# Window.net
KiCad netlist of a schematic drawn in EAGLE
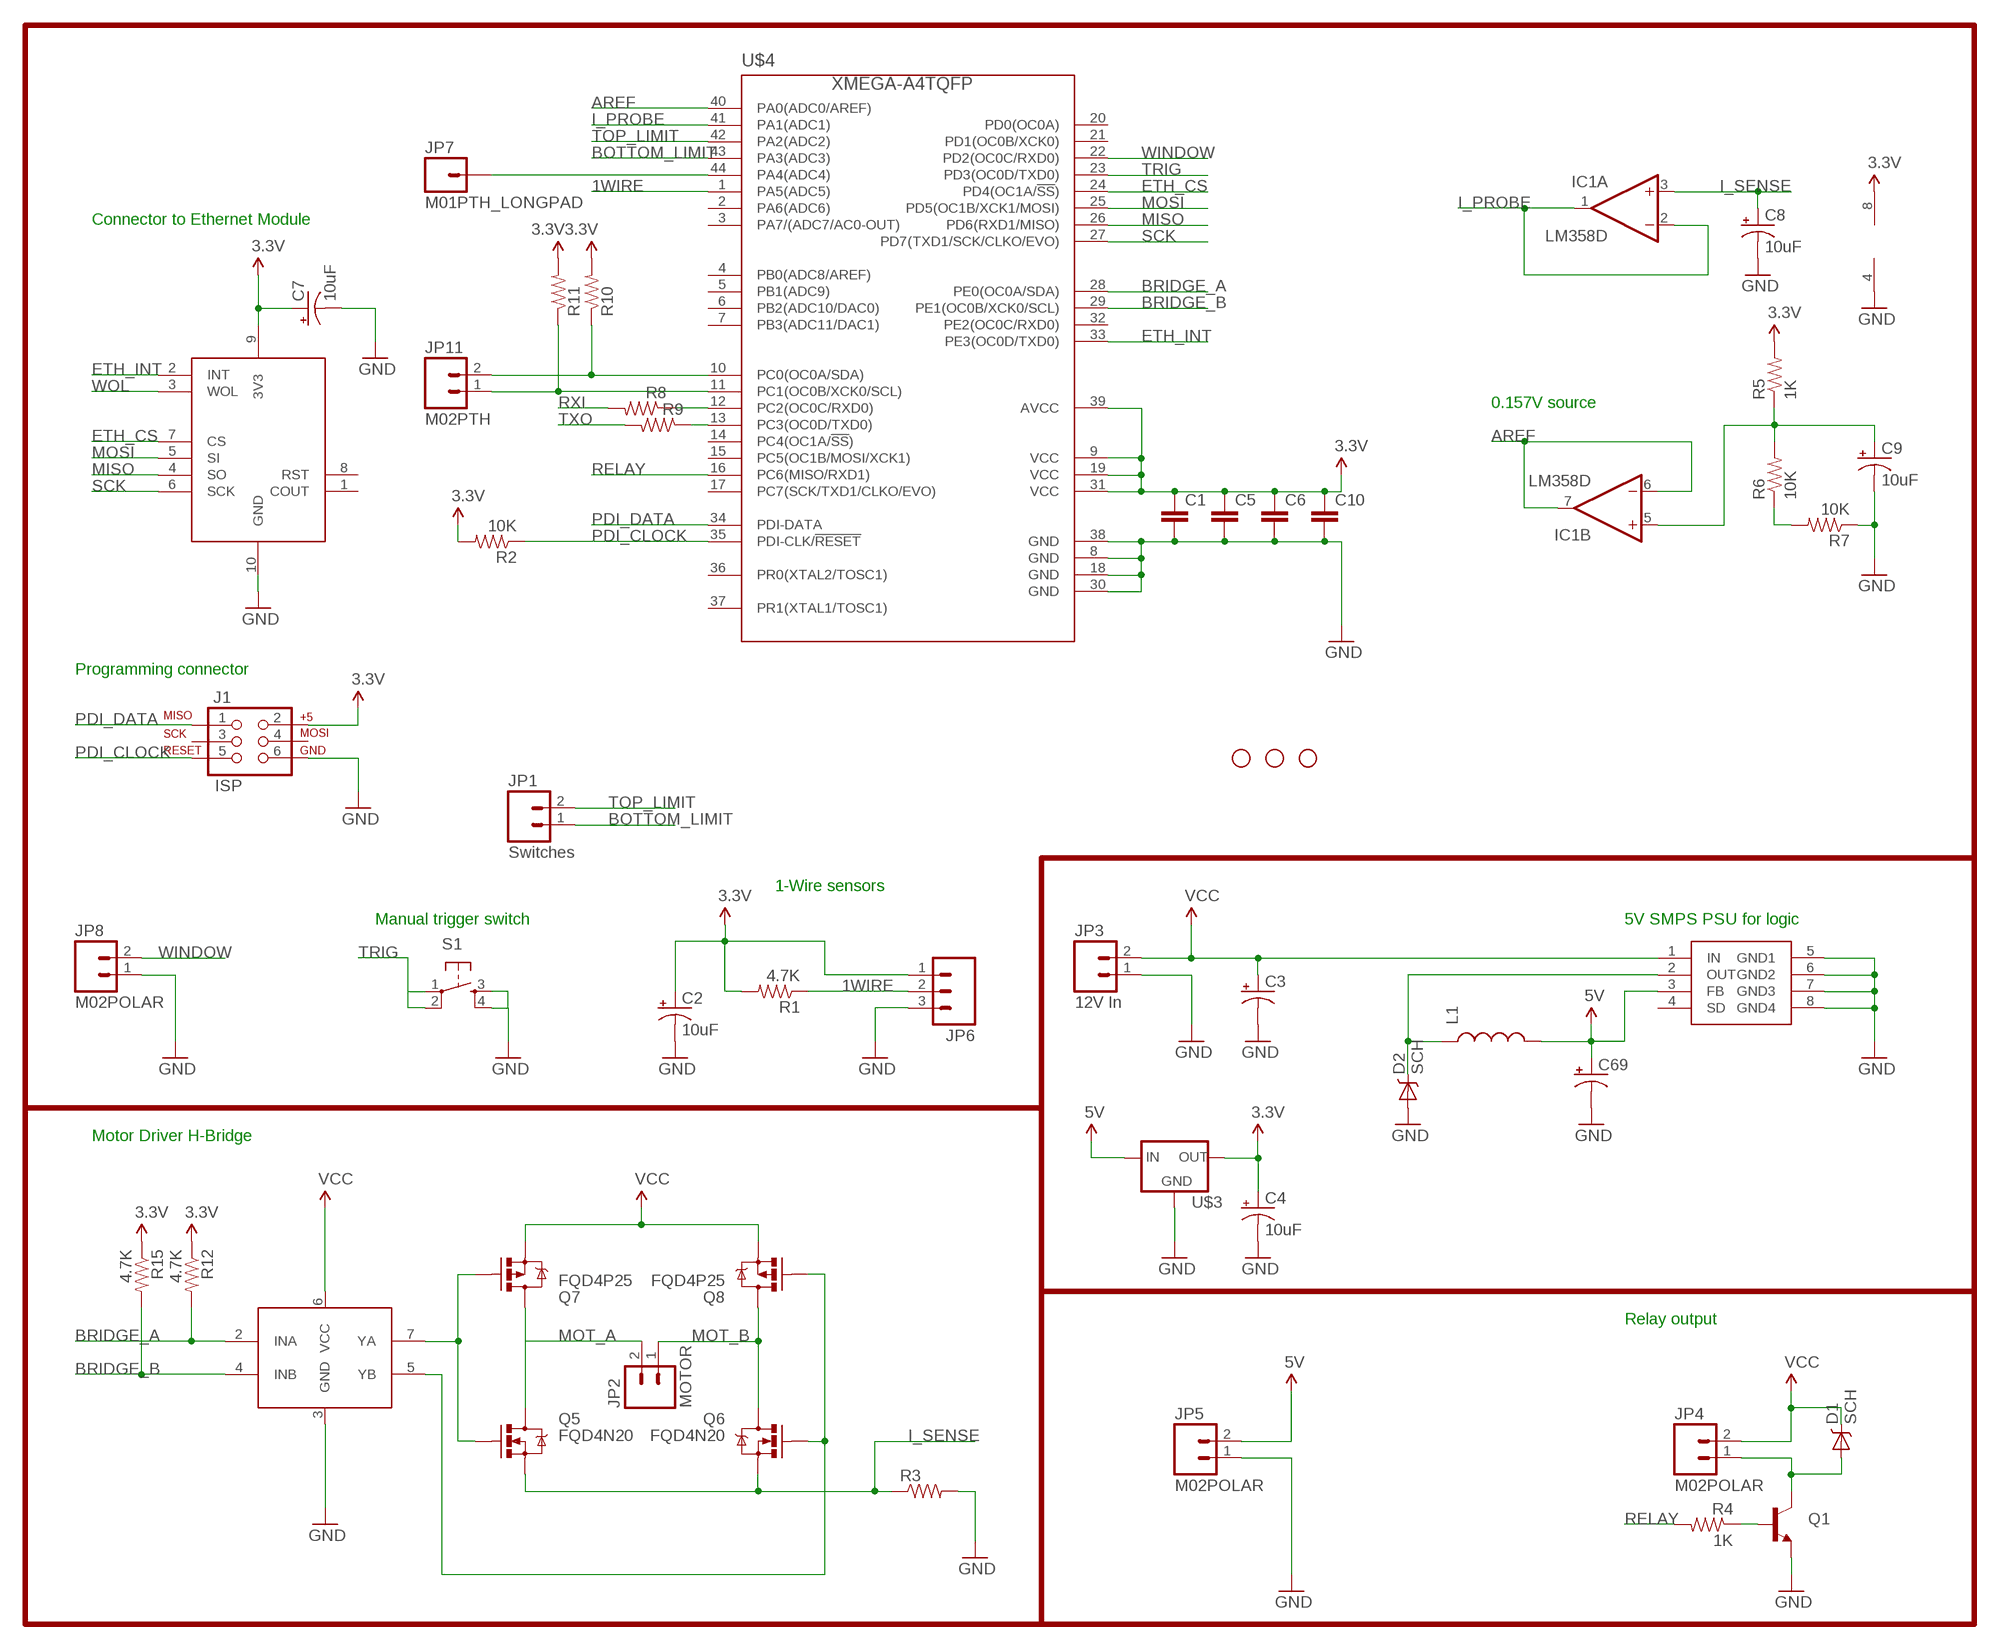
[diagram p0: schematic, sheet 1, part 1 of 2]
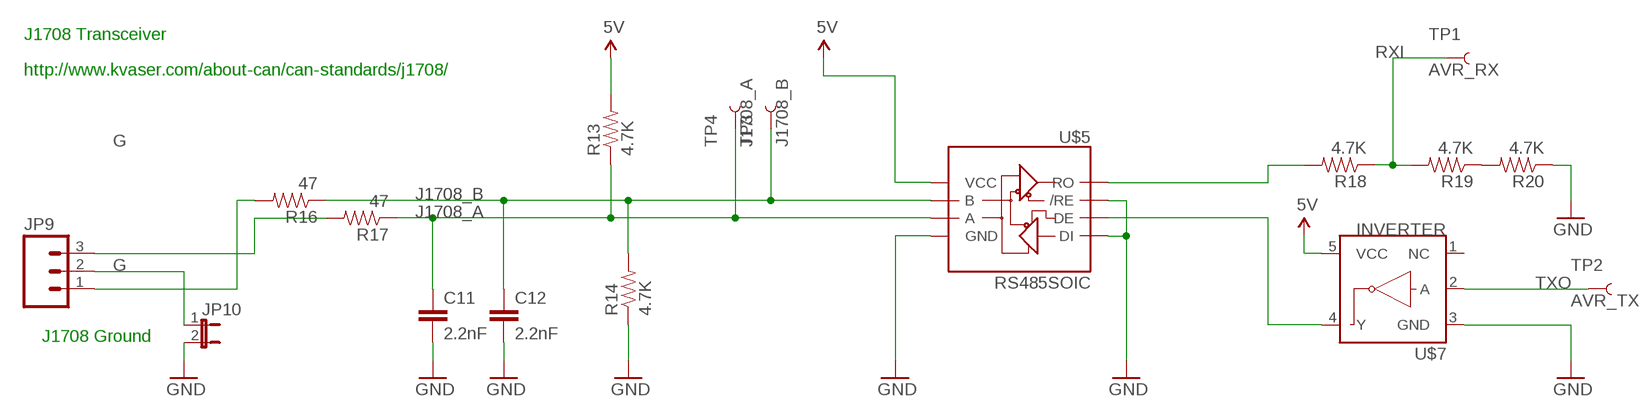
[diagram p1: schematic, sheet 1, part 2 of 2]

(export (version "E")
  (design (tool "Eeschema 10.0.6"))
  (components
    (comp (ref "C1")
      (value "CAP0603-CAP")
      (footprint "eagle-import:0603-CAP")
      (libsource (lib "eagle-import") (part "CAP0603-CAP"))
    )
    (comp (ref "C2")
      (value "10uF")
      (footprint "eagle-import:EIA3216")
      (libsource (lib "eagle-import") (part "CAP_POL1206"))
    )
    (comp (ref "C3")
      (value "CAP_POLPTH1")
      (footprint "eagle-import:CPOL-RADIAL-100UF-25V")
      (libsource (lib "eagle-import") (part "CAP_POLPTH1"))
    )
    (comp (ref "C4")
      (value "10uF")
      (footprint "eagle-import:EIA3216")
      (libsource (lib "eagle-import") (part "CAP_POL1206"))
    )
    (comp (ref "C5")
      (value "CAP0603-CAP")
      (footprint "eagle-import:0603-CAP")
      (libsource (lib "eagle-import") (part "CAP0603-CAP"))
    )
    (comp (ref "C6")
      (value "CAP0603-CAP")
      (footprint "eagle-import:0603-CAP")
      (libsource (lib "eagle-import") (part "CAP0603-CAP"))
    )
    (comp (ref "C7")
      (value "10uF")
      (footprint "eagle-import:EIA3216")
      (libsource (lib "eagle-import") (part "CAP_POL1206"))
    )
    (comp (ref "C8")
      (value "10uF")
      (footprint "eagle-import:EIA3216")
      (libsource (lib "eagle-import") (part "CAP_POL1206"))
    )
    (comp (ref "C9")
      (value "10uF")
      (footprint "eagle-import:EIA3216")
      (libsource (lib "eagle-import") (part "CAP_POL1206"))
    )
    (comp (ref "C10")
      (value "CAP0603-CAP")
      (footprint "eagle-import:0603-CAP")
      (libsource (lib "eagle-import") (part "CAP0603-CAP"))
    )
    (comp (ref "C11")
      (value "2.2nF")
      (footprint "eagle-import:0603-CAP")
      (libsource (lib "eagle-import") (part "CAP0603-CAP"))
    )
    (comp (ref "C12")
      (value "2.2nF")
      (footprint "eagle-import:0603-CAP")
      (libsource (lib "eagle-import") (part "CAP0603-CAP"))
    )
    (comp (ref "C69")
      (value "CAP_POLPTH1")
      (footprint "eagle-import:CPOL-RADIAL-100UF-25V")
      (libsource (lib "eagle-import") (part "CAP_POLPTH1"))
    )
    (comp (ref "D1")
      (value "SCH")
      (footprint "eagle-import:SMA-DIODE")
      (libsource (lib "eagle-import") (part "DIODE-SCHOTTKY_"))
    )
    (comp (ref "D2")
      (value "SCH")
      (footprint "eagle-import:SMA-DIODE")
      (libsource (lib "eagle-import") (part "DIODE-SCHOTTKY_"))
    )
    (comp (ref "IC1")
      (value "LM358D")
      (footprint "eagle-import:SO08")
      (libsource (lib "eagle-import") (part "LM358D"))
    )
    (comp (ref "J1")
      (value "ISP")
      (footprint "eagle-import:2X3")
      (libsource (lib "eagle-import") (part "AVR_SPI_PRG_6PTH"))
    )
    (comp (ref "JP1")
      (value "Switches")
      (footprint "eagle-import:SCREWTERMINAL-3.5MM-2")
      (libsource (lib "eagle-import") (part "M023.5MM"))
    )
    (comp (ref "JP2")
      (value "MOTOR")
      (footprint "eagle-import:SCREWTERMINAL-3.5MM-2")
      (libsource (lib "eagle-import") (part "M023.5MM"))
    )
    (comp (ref "JP3")
      (value "12V In")
      (footprint "eagle-import:SCREWTERMINAL-3.5MM-2")
      (libsource (lib "eagle-import") (part "M023.5MM"))
    )
    (comp (ref "JP4")
      (value "M02POLAR")
      (footprint "eagle-import:MOLEX-1X2")
      (libsource (lib "eagle-import") (part "M02POLAR"))
    )
    (comp (ref "JP5")
      (value "M02POLAR")
      (footprint "eagle-import:MOLEX-1X2")
      (libsource (lib "eagle-import") (part "M02POLAR"))
    )
    (comp (ref "JP6")
      (value "M03POLAR")
      (footprint "eagle-import:MOLEX-1X3")
      (libsource (lib "eagle-import") (part "M03POLAR"))
    )
    (comp (ref "JP7")
      (value "M01PTH_LONGPAD")
      (footprint "eagle-import:1X01_LONGPAD")
      (libsource (lib "eagle-import") (part "M01PTH_LONGPAD"))
    )
    (comp (ref "JP8")
      (value "M02POLAR")
      (footprint "eagle-import:MOLEX-1X2")
      (libsource (lib "eagle-import") (part "M02POLAR"))
    )
    (comp (ref "JP9")
      (value "M03POLAR")
      (footprint "eagle-import:MOLEX-1X3")
      (libsource (lib "eagle-import") (part "M03POLAR"))
    )
    (comp (ref "JP10")
      (value "JUMPER-2PTH")
      (footprint "eagle-import:1X02")
      (libsource (lib "eagle-import") (part "JUMPER-2PTH"))
    )
    (comp (ref "JP11")
      (value "M02PTH")
      (footprint "eagle-import:1X02")
      (libsource (lib "eagle-import") (part "M02PTH"))
    )
    (comp (ref "L1")
      (value "INDUCTOR1206H*")
      (footprint "eagle-import:INDUCTOR-1206")
      (libsource (lib "eagle-import") (part "INDUCTORH1206"))
    )
    (comp (ref "Q1")
      (value "TRANSISTOR_NPNSOT23")
      (footprint "eagle-import:SOT23")
      (libsource (lib "eagle-import") (part "TRANSISTOR_NPNSOT23"))
    )
    (comp (ref "Q5")
      (value "FQD4N20")
      (footprint "eagle-import:DPAK")
      (libsource (lib "eagle-import") (part "MOSFET-NCHANNELFDD8780"))
    )
    (comp (ref "Q6")
      (value "FQD4N20")
      (footprint "eagle-import:DPAK")
      (libsource (lib "eagle-import") (part "MOSFET-NCHANNELFDD8780"))
    )
    (comp (ref "Q7")
      (value "FQD4P25")
      (footprint "eagle-import:DPAK")
      (libsource (lib "eagle-import") (part "MOSFET-PCHANNEL"))
    )
    (comp (ref "Q8")
      (value "FQD4P25")
      (footprint "eagle-import:DPAK")
      (libsource (lib "eagle-import") (part "MOSFET-PCHANNEL"))
    )
    (comp (ref "R1")
      (value "4.7K")
      (footprint "eagle-import:1206")
      (libsource (lib "eagle-import") (part "RESISTOR1206"))
    )
    (comp (ref "R2")
      (value "10K")
      (footprint "eagle-import:1206")
      (libsource (lib "eagle-import") (part "RESISTOR1206"))
    )
    (comp (ref "R3")
      (value "RESISTORPTH-1W")
      (footprint "eagle-import:AXIAL-0.6")
      (libsource (lib "eagle-import") (part "RESISTORPTH-1W"))
    )
    (comp (ref "R4")
      (value "1K")
      (footprint "eagle-import:1206")
      (libsource (lib "eagle-import") (part "RESISTOR1206"))
    )
    (comp (ref "R5")
      (value "1K")
      (footprint "eagle-import:1206")
      (libsource (lib "eagle-import") (part "RESISTOR1206"))
    )
    (comp (ref "R6")
      (value "10K")
      (footprint "eagle-import:1206")
      (libsource (lib "eagle-import") (part "RESISTOR1206"))
    )
    (comp (ref "R7")
      (value "10K")
      (footprint "eagle-import:1206")
      (libsource (lib "eagle-import") (part "RESISTOR1206"))
    )
    (comp (ref "R8")
      (value "RESISTOR0603-RES")
      (footprint "eagle-import:0603-RES")
      (libsource (lib "eagle-import") (part "RESISTOR0603-RES"))
    )
    (comp (ref "R9")
      (value "RESISTOR0603-RES")
      (footprint "eagle-import:0603-RES")
      (libsource (lib "eagle-import") (part "RESISTOR0603-RES"))
    )
    (comp (ref "R10")
      (value "RESISTOR0603-RES")
      (footprint "eagle-import:0603-RES")
      (libsource (lib "eagle-import") (part "RESISTOR0603-RES"))
    )
    (comp (ref "R11")
      (value "RESISTOR0603-RES")
      (footprint "eagle-import:0603-RES")
      (libsource (lib "eagle-import") (part "RESISTOR0603-RES"))
    )
    (comp (ref "R12")
      (value "4.7K")
      (footprint "eagle-import:1206")
      (libsource (lib "eagle-import") (part "RESISTOR1206"))
    )
    (comp (ref "R13")
      (value "4.7K")
      (footprint "eagle-import:1206")
      (libsource (lib "eagle-import") (part "RESISTOR1206"))
    )
    (comp (ref "R14")
      (value "4.7K")
      (footprint "eagle-import:1206")
      (libsource (lib "eagle-import") (part "RESISTOR1206"))
    )
    (comp (ref "R15")
      (value "4.7K")
      (footprint "eagle-import:1206")
      (libsource (lib "eagle-import") (part "RESISTOR1206"))
    )
    (comp (ref "R16")
      (value "47")
      (footprint "eagle-import:1206")
      (libsource (lib "eagle-import") (part "RESISTOR1206"))
    )
    (comp (ref "R17")
      (value "47")
      (footprint "eagle-import:1206")
      (libsource (lib "eagle-import") (part "RESISTOR1206"))
    )
    (comp (ref "R18")
      (value "4.7K")
      (footprint "eagle-import:1206")
      (libsource (lib "eagle-import") (part "RESISTOR1206"))
    )
    (comp (ref "R19")
      (value "4.7K")
      (footprint "eagle-import:1206")
      (libsource (lib "eagle-import") (part "RESISTOR1206"))
    )
    (comp (ref "R20")
      (value "4.7K")
      (footprint "eagle-import:1206")
      (libsource (lib "eagle-import") (part "RESISTOR1206"))
    )
    (comp (ref "S1")
      (value "TAC_SWITCHPTH")
      (footprint "eagle-import:TACTILE-PTH")
      (libsource (lib "eagle-import") (part "TAC_SWITCHPTH"))
    )
    (comp (ref "STANDOFF2")
      (value "STAND-OFF")
      (footprint "eagle-import:STAND-OFF")
      (libsource (lib "eagle-import") (part "STAND-OFF"))
    )
    (comp (ref "STANDOFF3")
      (value "STAND-OFF")
      (footprint "eagle-import:STAND-OFF")
      (libsource (lib "eagle-import") (part "STAND-OFF"))
    )
    (comp (ref "STANDOFF4")
      (value "STAND-OFF")
      (footprint "eagle-import:STAND-OFF")
      (libsource (lib "eagle-import") (part "STAND-OFF"))
    )
    (comp (ref "TP1")
      (value "AVR_RX")
      (footprint "eagle-import:PAD.03X.05")
      (libsource (lib "eagle-import") (part "TEST-POINT3X5"))
    )
    (comp (ref "TP2")
      (value "AVR_TX")
      (footprint "eagle-import:PAD.03X.05")
      (libsource (lib "eagle-import") (part "TEST-POINT3X5"))
    )
    (comp (ref "TP3")
      (value "J1708_B")
      (footprint "eagle-import:PAD.03X.05")
      (libsource (lib "eagle-import") (part "TEST-POINT3X5"))
    )
    (comp (ref "TP4")
      (value "J1708_A")
      (footprint "eagle-import:PAD.03X.05")
      (libsource (lib "eagle-import") (part "TEST-POINT3X5"))
    )
    (comp (ref "U$1")
      (value "ETHMODULE")
      (footprint "eagle-import:2X5")
      (libsource (lib "eagle-import") (part "ETHMODULE"))
    )
    (comp (ref "U$2")
      (value "AP1509-33")
      (footprint "eagle-import:SOIC-8")
      (libsource (lib "eagle-import") (part "AP1509-33"))
    )
    (comp (ref "U$3")
      (value "V_REG_MIC2920")
      (footprint "eagle-import:SOT223")
      (libsource (lib "eagle-import") (part "V_REG_MIC2920"))
    )
    (comp (ref "U$4")
      (value "XMEGA-A4TQFP")
      (footprint "eagle-import:TQFP44")
      (libsource (lib "eagle-import") (part "XMEGA-A4TQFP"))
    )
    (comp (ref "U$5")
      (value "RS485SOIC")
      (footprint "eagle-import:SO08")
      (libsource (lib "eagle-import") (part "RS485SOIC"))
    )
    (comp (ref "U$6")
      (value "4427")
      (footprint "eagle-import:SOIC-8")
      (libsource (lib "eagle-import") (part "4427"))
    )
    (comp (ref "U$7")
      (value "INVERTER")
      (footprint "eagle-import:SOT23-5")
      (libsource (lib "eagle-import") (part "INVERTER"))
    )
  )
  (nets
    (net (code "1") (name "/1WIRE") (class "Default")
      (node (ref "JP6") (pin "2") (pinfunction "2_2") (pintype "passive"))
      (node (ref "R1") (pin "1") (pinfunction "1_1") (pintype "passive"))
      (node (ref "U$4") (pin "1") (pinfunction "PA5(ADC5)_1") (pintype "bidirectional"))
    )
    (net (code "2") (name "/AREF") (class "Default")
      (node (ref "IC1") (pin "6") (pinfunction "-IN_6") (pintype "input"))
      (node (ref "IC1") (pin "7") (pinfunction "OUT_7") (pintype "output"))
      (node (ref "U$4") (pin "40") (pinfunction "PA0(ADC0/AREF)_40") (pintype "bidirectional"))
    )
    (net (code "3") (name "/BOTTOM_LIMIT") (class "Default")
      (node (ref "JP1") (pin "1") (pinfunction "1_1") (pintype "passive"))
      (node (ref "U$4") (pin "43") (pinfunction "PA3(ADC3)_43") (pintype "bidirectional"))
    )
    (net (code "4") (name "/BRIDGE_A") (class "Default")
      (node (ref "R12") (pin "2") (pinfunction "2_2") (pintype "passive"))
      (node (ref "U$4") (pin "28") (pinfunction "PE0(OC0A/SDA)_28") (pintype "bidirectional"))
      (node (ref "U$6") (pin "2") (pinfunction "INA_2") (pintype "bidirectional"))
    )
    (net (code "5") (name "/BRIDGE_B") (class "Default")
      (node (ref "R15") (pin "2") (pinfunction "2_2") (pintype "passive"))
      (node (ref "U$4") (pin "29") (pinfunction "PE1(OC0B/XCK0/SCL)_29") (pintype "bidirectional"))
      (node (ref "U$6") (pin "4") (pinfunction "INB_4") (pintype "bidirectional"))
    )
    (net (code "6") (name "/COUT") (class "Default")
      (node (ref "U$1") (pin "1") (pinfunction "COUT_1") (pintype "power_in"))
    )
    (net (code "7") (name "/ETH_CS") (class "Default")
      (node (ref "U$1") (pin "7") (pinfunction "CS_7") (pintype "power_in"))
      (node (ref "U$4") (pin "24") (pinfunction "PD4(OC1A/~{SS})_24") (pintype "bidirectional"))
    )
    (net (code "8") (name "/ETH_INT") (class "Default")
      (node (ref "U$1") (pin "2") (pinfunction "INT_2") (pintype "power_in"))
      (node (ref "U$4") (pin "33") (pinfunction "PE3(OC0D/TXD0)_33") (pintype "bidirectional"))
    )
    (net (code "9") (name "/G") (class "Default")
      (node (ref "JP10") (pin "1") (pinfunction "1_1") (pintype "passive"))
      (node (ref "JP9") (pin "2") (pinfunction "2_2") (pintype "passive"))
    )
    (net (code "10") (name "/I_PROBE") (class "Default")
      (node (ref "IC1") (pin "1") (pinfunction "OUT_1") (pintype "output"))
      (node (ref "IC1") (pin "2") (pinfunction "-IN_2") (pintype "input"))
      (node (ref "U$4") (pin "41") (pinfunction "PA1(ADC1)_41") (pintype "bidirectional"))
    )
    (net (code "11") (name "/I_SENSE") (class "Default")
      (node (ref "C8") (pin "A") (pinfunction "+_A") (pintype "passive"))
      (node (ref "IC1") (pin "3") (pinfunction "+IN_3") (pintype "input"))
      (node (ref "Q5") (pin "3") (pinfunction "S_3") (pintype "passive"))
      (node (ref "Q6") (pin "3") (pinfunction "S_3") (pintype "passive"))
      (node (ref "R3") (pin "P$1") (pinfunction "1_P$1") (pintype "passive"))
    )
    (net (code "12") (name "/J1708_A") (class "Default")
      (node (ref "C11") (pin "1") (pinfunction "1_1") (pintype "passive"))
      (node (ref "R13") (pin "1") (pinfunction "1_1") (pintype "passive"))
      (node (ref "R17") (pin "1") (pinfunction "1_1") (pintype "passive"))
      (node (ref "TP4") (pin "P$1") (pinfunction "1_P$1") (pintype "bidirectional"))
      (node (ref "U$5") (pin "6") (pinfunction "A_6") (pintype "bidirectional"))
    )
    (net (code "13") (name "/J1708_B") (class "Default")
      (node (ref "C12") (pin "1") (pinfunction "1_1") (pintype "passive"))
      (node (ref "R14") (pin "2") (pinfunction "2_2") (pintype "passive"))
      (node (ref "R16") (pin "1") (pinfunction "1_1") (pintype "passive"))
      (node (ref "TP3") (pin "P$1") (pinfunction "1_P$1") (pintype "bidirectional"))
      (node (ref "U$5") (pin "7") (pinfunction "B_7") (pintype "bidirectional"))
    )
    (net (code "14") (name "/MISO") (class "Default")
      (node (ref "U$1") (pin "4") (pinfunction "SO_4") (pintype "power_in"))
      (node (ref "U$4") (pin "26") (pinfunction "PD6(RXD1/MISO)_26") (pintype "bidirectional"))
    )
    (net (code "15") (name "/MOSI") (class "Default")
      (node (ref "U$1") (pin "5") (pinfunction "SI_5") (pintype "power_in"))
      (node (ref "U$4") (pin "25") (pinfunction "PD5(OC1B/XCK1/MOSI)_25") (pintype "bidirectional"))
    )
    (net (code "16") (name "/MOT_A") (class "Default")
      (node (ref "JP2") (pin "2") (pinfunction "2_2") (pintype "passive"))
      (node (ref "Q5") (pin "4") (pinfunction "D_4") (pintype "passive"))
      (node (ref "Q7") (pin "4") (pinfunction "D_4") (pintype "passive"))
    )
    (net (code "17") (name "/MOT_B") (class "Default")
      (node (ref "JP2") (pin "1") (pinfunction "1_1") (pintype "passive"))
      (node (ref "Q6") (pin "4") (pinfunction "D_4") (pintype "passive"))
      (node (ref "Q8") (pin "4") (pinfunction "D_4") (pintype "passive"))
    )
    (net (code "18") (name "/PDI_CLOCK") (class "Default")
      (node (ref "J1") (pin "5") (pinfunction "5_5") (pintype "passive"))
      (node (ref "R2") (pin "1") (pinfunction "1_1") (pintype "passive"))
      (node (ref "U$4") (pin "35") (pinfunction "PDI-CLK/~{RESET}_35") (pintype "input"))
    )
    (net (code "19") (name "/PDI_DATA") (class "Default")
      (node (ref "J1") (pin "1") (pinfunction "1_1") (pintype "passive"))
      (node (ref "U$4") (pin "34") (pinfunction "PDI-DATA_34") (pintype "bidirectional"))
    )
    (net (code "20") (name "/RELAY") (class "Default")
      (node (ref "R4") (pin "2") (pinfunction "2_2") (pintype "passive"))
      (node (ref "U$4") (pin "16") (pinfunction "PC6(MISO/RXD1)_16") (pintype "bidirectional"))
    )
    (net (code "21") (name "/RST") (class "Default")
      (node (ref "U$1") (pin "8") (pinfunction "RST_8") (pintype "power_in"))
    )
    (net (code "22") (name "/RXI") (class "Default")
      (node (ref "R18") (pin "1") (pinfunction "1_1") (pintype "passive"))
      (node (ref "R19") (pin "2") (pinfunction "2_2") (pintype "passive"))
      (node (ref "R8") (pin "2") (pinfunction "2_2") (pintype "passive"))
      (node (ref "TP1") (pin "P$1") (pinfunction "1_P$1") (pintype "bidirectional"))
    )
    (net (code "23") (name "/SCK") (class "Default")
      (node (ref "U$1") (pin "6") (pinfunction "SCK_6") (pintype "power_in"))
      (node (ref "U$4") (pin "27") (pinfunction "PD7(TXD1/SCK/CLKO/EVO)_27") (pintype "bidirectional"))
    )
    (net (code "24") (name "/TOP_LIMIT") (class "Default")
      (node (ref "JP1") (pin "2") (pinfunction "2_2") (pintype "passive"))
      (node (ref "U$4") (pin "42") (pinfunction "PA2(ADC2)_42") (pintype "bidirectional"))
    )
    (net (code "25") (name "/TRIG") (class "Default")
      (node (ref "S1") (pin "1") (pinfunction "1_1") (pintype "passive"))
      (node (ref "S1") (pin "2") (pinfunction "2_2") (pintype "passive"))
      (node (ref "U$4") (pin "23") (pinfunction "PD3(OC0D/TXD0)_23") (pintype "bidirectional"))
    )
    (net (code "26") (name "/TXO") (class "Default")
      (node (ref "R9") (pin "2") (pinfunction "2_2") (pintype "passive"))
      (node (ref "TP2") (pin "P$1") (pinfunction "1_P$1") (pintype "bidirectional"))
      (node (ref "U$7") (pin "2") (pinfunction "A_2") (pintype "bidirectional"))
    )
    (net (code "27") (name "/WINDOW") (class "Default")
      (node (ref "JP8") (pin "2") (pinfunction "2_2") (pintype "passive"))
      (node (ref "U$4") (pin "22") (pinfunction "PD2(OC0C/RXD0)_22") (pintype "bidirectional"))
    )
    (net (code "28") (name "/WOL") (class "Default")
      (node (ref "U$1") (pin "3") (pinfunction "WOL_3") (pintype "power_in"))
    )
    (net (code "29") (name "3.3V") (class "Default")
      (node (ref "C1") (pin "1") (pinfunction "1_1") (pintype "passive"))
      (node (ref "C10") (pin "1") (pinfunction "1_1") (pintype "passive"))
      (node (ref "C2") (pin "A") (pinfunction "+_A") (pintype "passive"))
      (node (ref "C4") (pin "A") (pinfunction "+_A") (pintype "passive"))
      (node (ref "C5") (pin "1") (pinfunction "1_1") (pintype "passive"))
      (node (ref "C6") (pin "1") (pinfunction "1_1") (pintype "passive"))
      (node (ref "C7") (pin "A") (pinfunction "+_A") (pintype "passive"))
      (node (ref "IC1") (pin "8") (pinfunction "V+_8") (pintype "power_in"))
      (node (ref "J1") (pin "2") (pinfunction "2_2") (pintype "passive"))
      (node (ref "JP6") (pin "1") (pinfunction "1_1") (pintype "passive"))
      (node (ref "R1") (pin "2") (pinfunction "2_2") (pintype "passive"))
      (node (ref "R10") (pin "2") (pinfunction "2_2") (pintype "passive"))
      (node (ref "R11") (pin "2") (pinfunction "2_2") (pintype "passive"))
      (node (ref "R12") (pin "1") (pinfunction "1_1") (pintype "passive"))
      (node (ref "R15") (pin "1") (pinfunction "1_1") (pintype "passive"))
      (node (ref "R2") (pin "2") (pinfunction "2_2") (pintype "passive"))
      (node (ref "R5") (pin "2") (pinfunction "2_2") (pintype "passive"))
      (node (ref "U$1") (pin "9") (pinfunction "3V3_9") (pintype "power_in"))
      (node (ref "U$3") (pin "3") (pinfunction "OUT_3") (pintype "output"))
      (node (ref "U$4") (pin "19") (pinfunction "VCC_19") (pintype "power_in"))
      (node (ref "U$4") (pin "31") (pinfunction "VCC_31") (pintype "power_in"))
      (node (ref "U$4") (pin "39") (pinfunction "AVCC_39") (pintype "power_in"))
      (node (ref "U$4") (pin "9") (pinfunction "VCC_9") (pintype "power_in"))
    )
    (net (code "30") (name "5V") (class "Default")
      (node (ref "C69") (pin "1") (pinfunction "+_1") (pintype "passive"))
      (node (ref "JP5") (pin "2") (pinfunction "2_2") (pintype "passive"))
      (node (ref "L1") (pin "P$2") (pinfunction "2_P$2") (pintype "passive"))
      (node (ref "R13") (pin "2") (pinfunction "2_2") (pintype "passive"))
      (node (ref "U$2") (pin "3") (pinfunction "FB_3") (pintype "bidirectional"))
      (node (ref "U$3") (pin "1") (pinfunction "IN_1") (pintype "input"))
      (node (ref "U$5") (pin "8") (pinfunction "VCC_8") (pintype "bidirectional"))
      (node (ref "U$7") (pin "5") (pinfunction "VCC_5") (pintype "bidirectional"))
    )
    (net (code "31") (name "GND") (class "Default")
      (node (ref "C1") (pin "2") (pinfunction "2_2") (pintype "passive"))
      (node (ref "C10") (pin "2") (pinfunction "2_2") (pintype "passive"))
      (node (ref "C11") (pin "2") (pinfunction "2_2") (pintype "passive"))
      (node (ref "C12") (pin "2") (pinfunction "2_2") (pintype "passive"))
      (node (ref "C2") (pin "C") (pinfunction "-_C") (pintype "passive"))
      (node (ref "C3") (pin "2") (pinfunction "-_2") (pintype "passive"))
      (node (ref "C4") (pin "C") (pinfunction "-_C") (pintype "passive"))
      (node (ref "C5") (pin "2") (pinfunction "2_2") (pintype "passive"))
      (node (ref "C6") (pin "2") (pinfunction "2_2") (pintype "passive"))
      (node (ref "C69") (pin "2") (pinfunction "-_2") (pintype "passive"))
      (node (ref "C7") (pin "C") (pinfunction "-_C") (pintype "passive"))
      (node (ref "C8") (pin "C") (pinfunction "-_C") (pintype "passive"))
      (node (ref "C9") (pin "C") (pinfunction "-_C") (pintype "passive"))
      (node (ref "D2") (pin "A") (pinfunction "A_A") (pintype "passive"))
      (node (ref "IC1") (pin "4") (pinfunction "V-_4") (pintype "power_in"))
      (node (ref "J1") (pin "6") (pinfunction "6_6") (pintype "passive"))
      (node (ref "JP10") (pin "2") (pinfunction "2_2") (pintype "passive"))
      (node (ref "JP3") (pin "1") (pinfunction "1_1") (pintype "passive"))
      (node (ref "JP5") (pin "1") (pinfunction "1_1") (pintype "passive"))
      (node (ref "JP6") (pin "3") (pinfunction "3_3") (pintype "passive"))
      (node (ref "JP8") (pin "1") (pinfunction "1_1") (pintype "passive"))
      (node (ref "Q1") (pin "2") (pinfunction "E_2") (pintype "passive"))
      (node (ref "R14") (pin "1") (pinfunction "1_1") (pintype "passive"))
      (node (ref "R20") (pin "1") (pinfunction "1_1") (pintype "passive"))
      (node (ref "R3") (pin "P$2") (pinfunction "2_P$2") (pintype "passive"))
      (node (ref "R7") (pin "1") (pinfunction "1_1") (pintype "passive"))
      (node (ref "S1") (pin "3") (pinfunction "3_3") (pintype "passive"))
      (node (ref "S1") (pin "4") (pinfunction "4_4") (pintype "passive"))
      (node (ref "U$1") (pin "10") (pinfunction "GND_10") (pintype "power_in"))
      (node (ref "U$2") (pin "5") (pinfunction "GND1_5") (pintype "bidirectional"))
      (node (ref "U$2") (pin "6") (pinfunction "GND2_6") (pintype "bidirectional"))
      (node (ref "U$2") (pin "7") (pinfunction "GND3_7") (pintype "bidirectional"))
      (node (ref "U$2") (pin "8") (pinfunction "GND4_8") (pintype "bidirectional"))
      (node (ref "U$3") (pin "2") (pinfunction "GND_2") (pintype "input"))
      (node (ref "U$4") (pin "18") (pinfunction "GND_18") (pintype "power_in"))
      (node (ref "U$4") (pin "30") (pinfunction "GND_30") (pintype "power_in"))
      (node (ref "U$4") (pin "38") (pinfunction "GND_38") (pintype "power_in"))
      (node (ref "U$4") (pin "8") (pinfunction "GND_8") (pintype "power_in"))
      (node (ref "U$5") (pin "2") (pinfunction "/RE_2") (pintype "bidirectional"))
      (node (ref "U$5") (pin "4") (pinfunction "DI_4") (pintype "bidirectional"))
      (node (ref "U$5") (pin "5") (pinfunction "GND_5") (pintype "bidirectional"))
      (node (ref "U$6") (pin "3") (pinfunction "GND_3") (pintype "bidirectional"))
      (node (ref "U$7") (pin "3") (pinfunction "GND_3") (pintype "bidirectional"))
    )
    (net (code "32") (name "Net-(C9-+)") (class "Default")
      (node (ref "C9") (pin "A") (pinfunction "+_A") (pintype "passive"))
      (node (ref "IC1") (pin "5") (pinfunction "+IN_5") (pintype "input"))
      (node (ref "R5") (pin "1") (pinfunction "1_1") (pintype "passive"))
      (node (ref "R6") (pin "2") (pinfunction "2_2") (pintype "passive"))
    )
    (net (code "33") (name "Net-(JP9-Pad1)") (class "Default")
      (node (ref "JP9") (pin "1") (pinfunction "1_1") (pintype "passive"))
      (node (ref "R16") (pin "2") (pinfunction "2_2") (pintype "passive"))
    )
    (net (code "34") (name "Net-(JP9-Pad3)") (class "Default")
      (node (ref "JP9") (pin "3") (pinfunction "3_3") (pintype "passive"))
      (node (ref "R17") (pin "2") (pinfunction "2_2") (pintype "passive"))
    )
    (net (code "35") (name "Net-(L1-1)") (class "Default")
      (node (ref "D2") (pin "C") (pinfunction "C_C") (pintype "passive"))
      (node (ref "L1") (pin "P$1") (pinfunction "1_P$1") (pintype "passive"))
      (node (ref "U$2") (pin "2") (pinfunction "OUT_2") (pintype "bidirectional"))
    )
    (net (code "36") (name "Net-(Q1-B)") (class "Default")
      (node (ref "Q1") (pin "1") (pinfunction "B_1") (pintype "passive"))
      (node (ref "R4") (pin "1") (pinfunction "1_1") (pintype "passive"))
    )
    (net (code "37") (name "Net-(Q1-C)") (class "Default")
      (node (ref "D1") (pin "A") (pinfunction "A_A") (pintype "passive"))
      (node (ref "JP4") (pin "1") (pinfunction "1_1") (pintype "passive"))
      (node (ref "Q1") (pin "3") (pinfunction "C_3") (pintype "passive"))
    )
    (net (code "38") (name "Net-(Q5-G)") (class "Default")
      (node (ref "Q5") (pin "1") (pinfunction "G_1") (pintype "passive"))
      (node (ref "Q7") (pin "1") (pinfunction "G_1") (pintype "passive"))
      (node (ref "U$6") (pin "7") (pinfunction "YA_7") (pintype "bidirectional"))
    )
    (net (code "39") (name "Net-(Q6-G)") (class "Default")
      (node (ref "Q6") (pin "1") (pinfunction "G_1") (pintype "passive"))
      (node (ref "Q8") (pin "1") (pinfunction "G_1") (pintype "passive"))
      (node (ref "U$6") (pin "5") (pinfunction "YB_5") (pintype "bidirectional"))
    )
    (net (code "40") (name "Net-(R6-Pad1)") (class "Default")
      (node (ref "R6") (pin "1") (pinfunction "1_1") (pintype "passive"))
      (node (ref "R7") (pin "2") (pinfunction "2_2") (pintype "passive"))
    )
    (net (code "41") (name "Net-(R19-Pad1)") (class "Default")
      (node (ref "R19") (pin "1") (pinfunction "1_1") (pintype "passive"))
      (node (ref "R20") (pin "2") (pinfunction "2_2") (pintype "passive"))
    )
    (net (code "42") (name "Net-(U$4-PA4(ADC4))") (class "Default")
      (node (ref "JP7") (pin "1") (pinfunction "1_1") (pintype "passive"))
      (node (ref "U$4") (pin "44") (pinfunction "PA4(ADC4)_44") (pintype "bidirectional"))
    )
    (net (code "43") (name "Net-(U$4-PC0(OC0A{slash}SDA))") (class "Default")
      (node (ref "JP11") (pin "2") (pinfunction "2_2") (pintype "passive"))
      (node (ref "R10") (pin "1") (pinfunction "1_1") (pintype "passive"))
      (node (ref "U$4") (pin "10") (pinfunction "PC0(OC0A/SDA)_10") (pintype "bidirectional"))
    )
    (net (code "44") (name "Net-(U$4-PC1(OC0B{slash}XCK0{slash}SCL))") (class "Default")
      (node (ref "JP11") (pin "1") (pinfunction "1_1") (pintype "passive"))
      (node (ref "R11") (pin "1") (pinfunction "1_1") (pintype "passive"))
      (node (ref "U$4") (pin "11") (pinfunction "PC1(OC0B/XCK0/SCL)_11") (pintype "bidirectional"))
    )
    (net (code "45") (name "Net-(U$4-PC2(OC0C{slash}RXD0))") (class "Default")
      (node (ref "R8") (pin "1") (pinfunction "1_1") (pintype "passive"))
      (node (ref "U$4") (pin "12") (pinfunction "PC2(OC0C/RXD0)_12") (pintype "bidirectional"))
    )
    (net (code "46") (name "Net-(U$4-PC3(OC0D{slash}TXD0))") (class "Default")
      (node (ref "R9") (pin "1") (pinfunction "1_1") (pintype "passive"))
      (node (ref "U$4") (pin "13") (pinfunction "PC3(OC0D/TXD0)_13") (pintype "bidirectional"))
    )
    (net (code "47") (name "Net-(U$5-DE)") (class "Default")
      (node (ref "U$5") (pin "3") (pinfunction "DE_3") (pintype "bidirectional"))
      (node (ref "U$7") (pin "4") (pinfunction "Y_4") (pintype "bidirectional"))
    )
    (net (code "48") (name "Net-(U$5-RO)") (class "Default")
      (node (ref "R18") (pin "2") (pinfunction "2_2") (pintype "passive"))
      (node (ref "U$5") (pin "1") (pinfunction "RO_1") (pintype "bidirectional"))
    )
    (net (code "49") (name "VCC") (class "Default")
      (node (ref "C3") (pin "1") (pinfunction "+_1") (pintype "passive"))
      (node (ref "D1") (pin "C") (pinfunction "C_C") (pintype "passive"))
      (node (ref "JP3") (pin "2") (pinfunction "2_2") (pintype "passive"))
      (node (ref "JP4") (pin "2") (pinfunction "2_2") (pintype "passive"))
      (node (ref "Q7") (pin "3") (pinfunction "S_3") (pintype "passive"))
      (node (ref "Q8") (pin "3") (pinfunction "S_3") (pintype "passive"))
      (node (ref "U$2") (pin "1") (pinfunction "IN_1") (pintype "bidirectional"))
      (node (ref "U$6") (pin "6") (pinfunction "VCC_6") (pintype "bidirectional"))
    )
    (net (code "50") (name "unconnected-(J1-Pad3)") (class "Default")
      (node (ref "J1") (pin "3") (pinfunction "3_3") (pintype "passive"))
    )
    (net (code "51") (name "unconnected-(J1-Pad4)") (class "Default")
      (node (ref "J1") (pin "4") (pinfunction "4_4") (pintype "passive"))
    )
    (net (code "52") (name "unconnected-(U$2-SD-Pad4)") (class "Default")
      (node (ref "U$2") (pin "4") (pinfunction "SD_4") (pintype "bidirectional"))
    )
    (net (code "53") (name "unconnected-(U$4-PA6(ADC6)-Pad2)") (class "Default")
      (node (ref "U$4") (pin "2") (pinfunction "PA6(ADC6)_2") (pintype "bidirectional"))
    )
    (net (code "54") (name "unconnected-(U$4-PA7{slash}(ADC7{slash}AC0-OUT)-Pad3)") (class "Default")
      (node (ref "U$4") (pin "3") (pinfunction "PA7/(ADC7/AC0-OUT)_3") (pintype "bidirectional"))
    )
    (net (code "55") (name "unconnected-(U$4-PB0(ADC8{slash}AREF)-Pad4)") (class "Default")
      (node (ref "U$4") (pin "4") (pinfunction "PB0(ADC8/AREF)_4") (pintype "bidirectional"))
    )
    (net (code "56") (name "unconnected-(U$4-PB1(ADC9)-Pad5)") (class "Default")
      (node (ref "U$4") (pin "5") (pinfunction "PB1(ADC9)_5") (pintype "bidirectional"))
    )
    (net (code "57") (name "unconnected-(U$4-PB2(ADC10{slash}DAC0)-Pad6)") (class "Default")
      (node (ref "U$4") (pin "6") (pinfunction "PB2(ADC10/DAC0)_6") (pintype "bidirectional"))
    )
    (net (code "58") (name "unconnected-(U$4-PB3(ADC11{slash}DAC1)-Pad7)") (class "Default")
      (node (ref "U$4") (pin "7") (pinfunction "PB3(ADC11/DAC1)_7") (pintype "bidirectional"))
    )
    (net (code "59") (name "unconnected-(U$4-PC4(OC1A{slash}~{SS})-Pad14)") (class "Default")
      (node (ref "U$4") (pin "14") (pinfunction "PC4(OC1A/~{SS})_14") (pintype "bidirectional"))
    )
    (net (code "60") (name "unconnected-(U$4-PC5(OC1B{slash}MOSI{slash}XCK1)-Pad15)") (class "Default")
      (node (ref "U$4") (pin "15") (pinfunction "PC5(OC1B/MOSI/XCK1)_15") (pintype "bidirectional"))
    )
    (net (code "61") (name "unconnected-(U$4-PC7(SCK{slash}TXD1{slash}CLKO{slash}EVO)-Pad17)") (class "Default")
      (node (ref "U$4") (pin "17") (pinfunction "PC7(SCK/TXD1/CLKO/EVO)_17") (pintype "bidirectional"))
    )
    (net (code "62") (name "unconnected-(U$4-PD0(OC0A)-Pad20)") (class "Default")
      (node (ref "U$4") (pin "20") (pinfunction "PD0(OC0A)_20") (pintype "bidirectional"))
    )
    (net (code "63") (name "unconnected-(U$4-PD1(OC0B{slash}XCK0)-Pad21)") (class "Default")
      (node (ref "U$4") (pin "21") (pinfunction "PD1(OC0B/XCK0)_21") (pintype "bidirectional"))
    )
    (net (code "64") (name "unconnected-(U$4-PE2(OC0C{slash}RXD0)-Pad32)") (class "Default")
      (node (ref "U$4") (pin "32") (pinfunction "PE2(OC0C/RXD0)_32") (pintype "bidirectional"))
    )
    (net (code "65") (name "unconnected-(U$4-PR0(XTAL2{slash}TOSC1)-Pad36)") (class "Default")
      (node (ref "U$4") (pin "36") (pinfunction "PR0(XTAL2/TOSC1)_36") (pintype "bidirectional"))
    )
    (net (code "66") (name "unconnected-(U$4-PR1(XTAL1{slash}TOSC1)-Pad37)") (class "Default")
      (node (ref "U$4") (pin "37") (pinfunction "PR1(XTAL1/TOSC1)_37") (pintype "bidirectional"))
    )
    (net (code "67") (name "unconnected-(U$7-NC-Pad1)") (class "Default")
      (node (ref "U$7") (pin "1") (pinfunction "NC_1") (pintype "bidirectional"))
    )
  )
)
